# LEOPADMINI.net
KiCad netlist of a schematic drawn in EAGLE
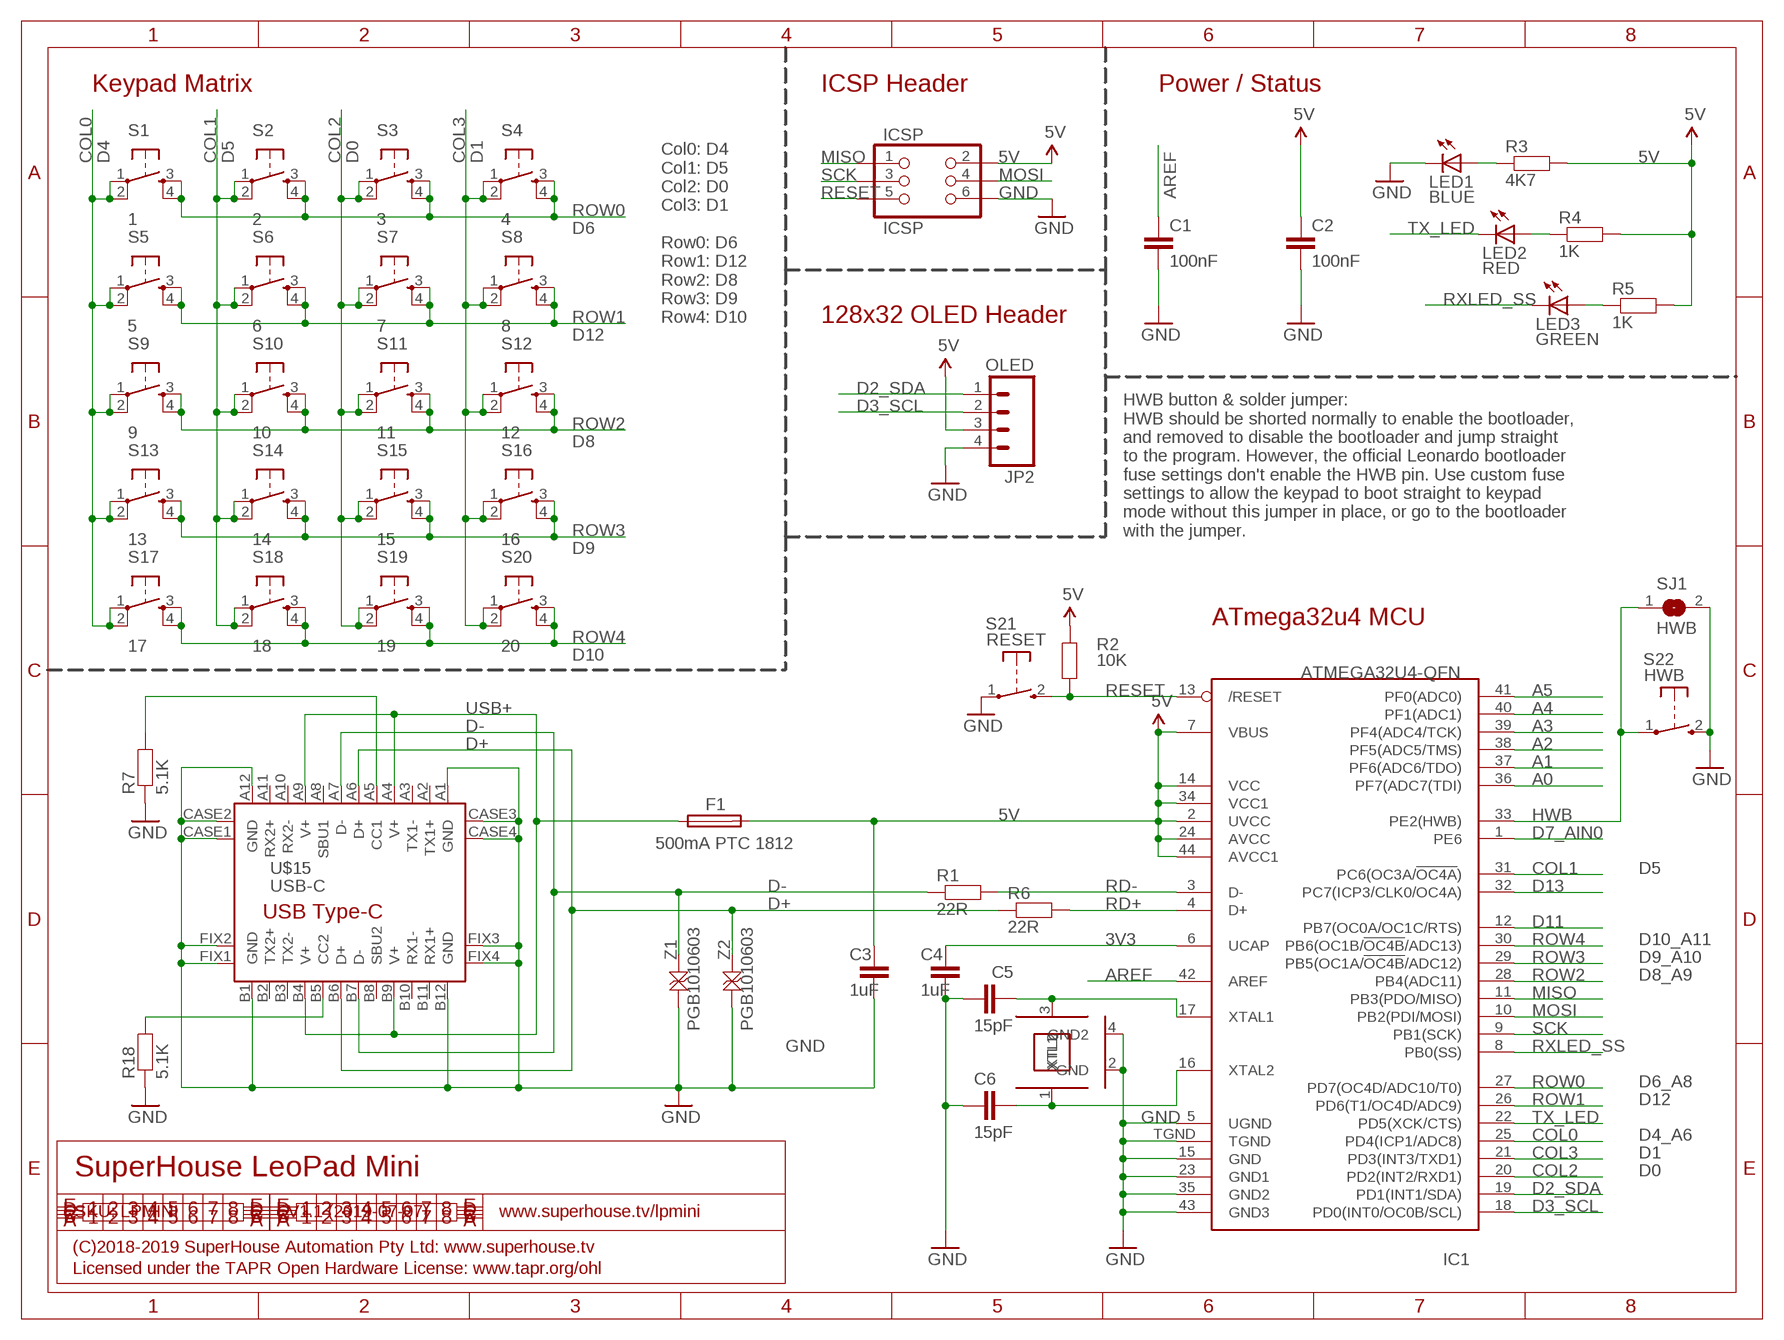
[diagram p0: schematic, sheet 1]

(export (version "E")
  (design (tool "Eeschema 10.0.6"))
  (components
    (comp (ref "C1")
      (value "100nF")
      (footprint "eagle-import:C0603")
      (libsource (lib "eagle-import") (part "CAP0603"))
    )
    (comp (ref "C2")
      (value "100nF")
      (footprint "eagle-import:C0603")
      (libsource (lib "eagle-import") (part "CAP0603"))
    )
    (comp (ref "C3")
      (value "1uF")
      (footprint "eagle-import:C0603")
      (libsource (lib "eagle-import") (part "CAP0603"))
    )
    (comp (ref "C4")
      (value "1uF")
      (footprint "eagle-import:C0603")
      (libsource (lib "eagle-import") (part "CAP0603"))
    )
    (comp (ref "C5")
      (value "15pF")
      (footprint "eagle-import:C0603")
      (libsource (lib "eagle-import") (part "CAP0603"))
    )
    (comp (ref "C6")
      (value "15pF")
      (footprint "eagle-import:C0603")
      (libsource (lib "eagle-import") (part "CAP0603"))
    )
    (comp (ref "F1")
      (value "500mA PTC 1812")
      (footprint "eagle-import:1812")
      (libsource (lib "eagle-import") (part "PTC050"))
    )
    (comp (ref "IC1")
      (value "ATMEGA32U4-QFN")
      (footprint "eagle-import:QFN-44N")
      (libsource (lib "eagle-import") (part "ATMEGA32U4-QFN"))
    )
    (comp (ref "ICSP")
      (value "ICSP")
      (footprint "eagle-import:2X03PTH")
      (libsource (lib "eagle-import") (part "ICSPPTH"))
    )
    (comp (ref "JP2")
      (value "OLED")
      (footprint "eagle-import:1X04")
      (libsource (lib "eagle-import") (part "M04PTH"))
    )
    (comp (ref "LED1")
      (value "BLUE")
      (footprint "eagle-import:LED-0603")
      (libsource (lib "eagle-import") (part "LED0603"))
    )
    (comp (ref "LED2")
      (value "RED")
      (footprint "eagle-import:LED-0603")
      (libsource (lib "eagle-import") (part "LED0603"))
    )
    (comp (ref "LED3")
      (value "GREEN")
      (footprint "eagle-import:LED-0603")
      (libsource (lib "eagle-import") (part "LED0603"))
    )
    (comp (ref "R1")
      (value "22R")
      (footprint "eagle-import:R0603")
      (libsource (lib "eagle-import") (part "RESISTOR0603"))
    )
    (comp (ref "R2")
      (value "10K")
      (footprint "eagle-import:R0603")
      (libsource (lib "eagle-import") (part "RESISTOR0603"))
    )
    (comp (ref "R3")
      (value "4K7")
      (footprint "eagle-import:R0603")
      (libsource (lib "eagle-import") (part "RESISTOR0603"))
    )
    (comp (ref "R4")
      (value "1K")
      (footprint "eagle-import:R0603")
      (libsource (lib "eagle-import") (part "RESISTOR0603"))
    )
    (comp (ref "R5")
      (value "1K")
      (footprint "eagle-import:R0603")
      (libsource (lib "eagle-import") (part "RESISTOR0603"))
    )
    (comp (ref "R6")
      (value "22R")
      (footprint "eagle-import:R0603")
      (libsource (lib "eagle-import") (part "RESISTOR0603"))
    )
    (comp (ref "R7")
      (value "5.1K")
      (footprint "eagle-import:R0603")
      (libsource (lib "eagle-import") (part "RESISTOR0603"))
    )
    (comp (ref "R18")
      (value "5.1K")
      (footprint "eagle-import:R0603")
      (libsource (lib "eagle-import") (part "RESISTOR0603"))
    )
    (comp (ref "S1")
      (value "1")
      (footprint "eagle-import:TACTILE-PTH-6MM")
      (fields (field (name "SPICEPREFIX") "S"))
      (libsource (lib "eagle-import") (part "TAC_SWITCH-PTH-6"))
    )
    (comp (ref "S2")
      (value "2")
      (footprint "eagle-import:TACTILE-PTH-6MM")
      (libsource (lib "eagle-import") (part "TAC_SWITCH-PTH-6"))
    )
    (comp (ref "S3")
      (value "3")
      (footprint "eagle-import:TACTILE-PTH-6MM")
      (libsource (lib "eagle-import") (part "TAC_SWITCH-PTH-6"))
    )
    (comp (ref "S4")
      (value "4")
      (footprint "eagle-import:TACTILE-PTH-6MM")
      (libsource (lib "eagle-import") (part "TAC_SWITCH-PTH-6"))
    )
    (comp (ref "S5")
      (value "5")
      (footprint "eagle-import:TACTILE-PTH-6MM")
      (libsource (lib "eagle-import") (part "TAC_SWITCH-PTH-6"))
    )
    (comp (ref "S6")
      (value "6")
      (footprint "eagle-import:TACTILE-PTH-6MM")
      (libsource (lib "eagle-import") (part "TAC_SWITCH-PTH-6"))
    )
    (comp (ref "S7")
      (value "7")
      (footprint "eagle-import:TACTILE-PTH-6MM")
      (libsource (lib "eagle-import") (part "TAC_SWITCH-PTH-6"))
    )
    (comp (ref "S8")
      (value "8")
      (footprint "eagle-import:TACTILE-PTH-6MM")
      (libsource (lib "eagle-import") (part "TAC_SWITCH-PTH-6"))
    )
    (comp (ref "S9")
      (value "9")
      (footprint "eagle-import:TACTILE-PTH-6MM")
      (libsource (lib "eagle-import") (part "TAC_SWITCH-PTH-6"))
    )
    (comp (ref "S10")
      (value "10")
      (footprint "eagle-import:TACTILE-PTH-6MM")
      (libsource (lib "eagle-import") (part "TAC_SWITCH-PTH-6"))
    )
    (comp (ref "S11")
      (value "11")
      (footprint "eagle-import:TACTILE-PTH-6MM")
      (libsource (lib "eagle-import") (part "TAC_SWITCH-PTH-6"))
    )
    (comp (ref "S12")
      (value "12")
      (footprint "eagle-import:TACTILE-PTH-6MM")
      (libsource (lib "eagle-import") (part "TAC_SWITCH-PTH-6"))
    )
    (comp (ref "S13")
      (value "13")
      (footprint "eagle-import:TACTILE-PTH-6MM")
      (libsource (lib "eagle-import") (part "TAC_SWITCH-PTH-6"))
    )
    (comp (ref "S14")
      (value "14")
      (footprint "eagle-import:TACTILE-PTH-6MM")
      (libsource (lib "eagle-import") (part "TAC_SWITCH-PTH-6"))
    )
    (comp (ref "S15")
      (value "15")
      (footprint "eagle-import:TACTILE-PTH-6MM")
      (libsource (lib "eagle-import") (part "TAC_SWITCH-PTH-6"))
    )
    (comp (ref "S16")
      (value "16")
      (footprint "eagle-import:TACTILE-PTH-6MM")
      (libsource (lib "eagle-import") (part "TAC_SWITCH-PTH-6"))
    )
    (comp (ref "S17")
      (value "17")
      (footprint "eagle-import:TACTILE-PTH-6MM")
      (libsource (lib "eagle-import") (part "TAC_SWITCH-PTH-6"))
    )
    (comp (ref "S18")
      (value "18")
      (footprint "eagle-import:TACTILE-PTH-6MM")
      (libsource (lib "eagle-import") (part "TAC_SWITCH-PTH-6"))
    )
    (comp (ref "S19")
      (value "19")
      (footprint "eagle-import:TACTILE-PTH-6MM")
      (libsource (lib "eagle-import") (part "TAC_SWITCH-PTH-6"))
    )
    (comp (ref "S20")
      (value "20")
      (footprint "eagle-import:TACTILE-PTH-6MM")
      (libsource (lib "eagle-import") (part "TAC_SWITCH-PTH-6"))
    )
    (comp (ref "S21")
      (value "RESET")
      (footprint "eagle-import:TACTILE_SMD_3X4X2")
      (libsource (lib "eagle-import") (part "TAC_SWITCH_2PINSMT"))
    )
    (comp (ref "S22")
      (value "HWB")
      (footprint "eagle-import:TACTILE_SMD_3X4X2")
      (libsource (lib "eagle-import") (part "TAC_SWITCH_2PINSMT"))
    )
    (comp (ref "SJ1")
      (value "HWB")
      (footprint "eagle-import:SJ")
      (libsource (lib "eagle-import") (part "SJN"))
    )
    (comp (ref "U$15")
      (value "USB-C")
      (footprint "eagle-import:USB-C-U52A")
      (libsource (lib "eagle-import") (part "USB-C"))
    )
    (comp (ref "XTL1")
      (value "16MHz")
      (footprint "eagle-import:CRYSTAL-SMD-3X2")
      (libsource (lib "eagle-import") (part "CRYSTAL-GND3X2"))
    )
    (comp (ref "Z1")
      (value "PGB1010603")
      (footprint "eagle-import:TVS0603")
      (libsource (lib "eagle-import") (part "TVS0603"))
    )
    (comp (ref "Z2")
      (value "PGB1010603")
      (footprint "eagle-import:TVS0603")
      (libsource (lib "eagle-import") (part "TVS0603"))
    )
  )
  (nets
    (net (code "1") (name "/3V3") (class "Default")
      (node (ref "C4") (pin "2") (pinfunction "2_2") (pintype "passive"))
      (node (ref "IC1") (pin "6") (pinfunction "UCAP_6") (pintype "bidirectional"))
    )
    (net (code "2") (name "/A0") (class "Default")
      (node (ref "IC1") (pin "36") (pinfunction "PF7(ADC7(TDI)_36") (pintype "bidirectional"))
    )
    (net (code "3") (name "/A1") (class "Default")
      (node (ref "IC1") (pin "37") (pinfunction "PF6(ADC6/TDO)_37") (pintype "bidirectional"))
    )
    (net (code "4") (name "/A2") (class "Default")
      (node (ref "IC1") (pin "38") (pinfunction "PF5(ADC5/TMS)_38") (pintype "bidirectional"))
    )
    (net (code "5") (name "/A3") (class "Default")
      (node (ref "IC1") (pin "39") (pinfunction "PF4(ADC4/TCK)_39") (pintype "bidirectional"))
    )
    (net (code "6") (name "/A4") (class "Default")
      (node (ref "IC1") (pin "40") (pinfunction "PF1(ADC1)_40") (pintype "bidirectional"))
    )
    (net (code "7") (name "/A5") (class "Default")
      (node (ref "IC1") (pin "41") (pinfunction "PF0(ADC0)_41") (pintype "bidirectional"))
    )
    (net (code "8") (name "/AREF") (class "Default")
      (node (ref "C1") (pin "1") (pinfunction "1_1") (pintype "passive"))
      (node (ref "IC1") (pin "42") (pinfunction "AREF_42") (pintype "bidirectional"))
    )
    (net (code "9") (name "/COL0") (class "Default")
      (node (ref "IC1") (pin "25") (pinfunction "PD4(ICP1/ADC8)_25") (pintype "bidirectional"))
      (node (ref "S1") (pin "1") (pinfunction "1_1") (pintype "passive"))
      (node (ref "S1") (pin "2") (pinfunction "2_2") (pintype "passive"))
      (node (ref "S13") (pin "1") (pinfunction "1_1") (pintype "passive"))
      (node (ref "S13") (pin "2") (pinfunction "2_2") (pintype "passive"))
      (node (ref "S17") (pin "1") (pinfunction "1_1") (pintype "passive"))
      (node (ref "S17") (pin "2") (pinfunction "2_2") (pintype "passive"))
      (node (ref "S5") (pin "1") (pinfunction "1_1") (pintype "passive"))
      (node (ref "S5") (pin "2") (pinfunction "2_2") (pintype "passive"))
      (node (ref "S9") (pin "1") (pinfunction "1_1") (pintype "passive"))
      (node (ref "S9") (pin "2") (pinfunction "2_2") (pintype "passive"))
    )
    (net (code "10") (name "/COL1") (class "Default")
      (node (ref "IC1") (pin "31") (pinfunction "PC6(OC3A/~{OC4A})_31") (pintype "bidirectional"))
      (node (ref "S10") (pin "1") (pinfunction "1_1") (pintype "passive"))
      (node (ref "S10") (pin "2") (pinfunction "2_2") (pintype "passive"))
      (node (ref "S14") (pin "1") (pinfunction "1_1") (pintype "passive"))
      (node (ref "S14") (pin "2") (pinfunction "2_2") (pintype "passive"))
      (node (ref "S18") (pin "1") (pinfunction "1_1") (pintype "passive"))
      (node (ref "S18") (pin "2") (pinfunction "2_2") (pintype "passive"))
      (node (ref "S2") (pin "1") (pinfunction "1_1") (pintype "passive"))
      (node (ref "S2") (pin "2") (pinfunction "2_2") (pintype "passive"))
      (node (ref "S6") (pin "1") (pinfunction "1_1") (pintype "passive"))
      (node (ref "S6") (pin "2") (pinfunction "2_2") (pintype "passive"))
    )
    (net (code "11") (name "/COL2") (class "Default")
      (node (ref "IC1") (pin "20") (pinfunction "PD2(INT2/RXD1)_20") (pintype "bidirectional"))
      (node (ref "S11") (pin "1") (pinfunction "1_1") (pintype "passive"))
      (node (ref "S11") (pin "2") (pinfunction "2_2") (pintype "passive"))
      (node (ref "S15") (pin "1") (pinfunction "1_1") (pintype "passive"))
      (node (ref "S15") (pin "2") (pinfunction "2_2") (pintype "passive"))
      (node (ref "S19") (pin "1") (pinfunction "1_1") (pintype "passive"))
      (node (ref "S19") (pin "2") (pinfunction "2_2") (pintype "passive"))
      (node (ref "S3") (pin "1") (pinfunction "1_1") (pintype "passive"))
      (node (ref "S3") (pin "2") (pinfunction "2_2") (pintype "passive"))
      (node (ref "S7") (pin "1") (pinfunction "1_1") (pintype "passive"))
      (node (ref "S7") (pin "2") (pinfunction "2_2") (pintype "passive"))
    )
    (net (code "12") (name "/COL3") (class "Default")
      (node (ref "IC1") (pin "21") (pinfunction "PD3(INT3/TXD1)_21") (pintype "bidirectional"))
      (node (ref "S12") (pin "1") (pinfunction "1_1") (pintype "passive"))
      (node (ref "S12") (pin "2") (pinfunction "2_2") (pintype "passive"))
      (node (ref "S16") (pin "1") (pinfunction "1_1") (pintype "passive"))
      (node (ref "S16") (pin "2") (pinfunction "2_2") (pintype "passive"))
      (node (ref "S20") (pin "1") (pinfunction "1_1") (pintype "passive"))
      (node (ref "S20") (pin "2") (pinfunction "2_2") (pintype "passive"))
      (node (ref "S4") (pin "1") (pinfunction "1_1") (pintype "passive"))
      (node (ref "S4") (pin "2") (pinfunction "2_2") (pintype "passive"))
      (node (ref "S8") (pin "1") (pinfunction "1_1") (pintype "passive"))
      (node (ref "S8") (pin "2") (pinfunction "2_2") (pintype "passive"))
    )
    (net (code "13") (name "/D+") (class "Default")
      (node (ref "R6") (pin "1") (pinfunction "1_1") (pintype "passive"))
      (node (ref "U$15") (pin "A6") (pinfunction "D+_A6") (pintype "bidirectional"))
      (node (ref "U$15") (pin "B6") (pinfunction "D+_B6") (pintype "bidirectional"))
      (node (ref "Z2") (pin "2") (pinfunction "2_2") (pintype "passive"))
    )
    (net (code "14") (name "/D-") (class "Default")
      (node (ref "R1") (pin "1") (pinfunction "1_1") (pintype "passive"))
      (node (ref "U$15") (pin "A7") (pinfunction "D-_A7") (pintype "bidirectional"))
      (node (ref "U$15") (pin "B7") (pinfunction "D-_B7") (pintype "bidirectional"))
      (node (ref "Z1") (pin "2") (pinfunction "2_2") (pintype "passive"))
    )
    (net (code "15") (name "/D2_SDA") (class "Default")
      (node (ref "IC1") (pin "19") (pinfunction "PD1(INT1/SDA)_19") (pintype "bidirectional"))
      (node (ref "JP2") (pin "1") (pinfunction "1_1") (pintype "passive"))
    )
    (net (code "16") (name "/D3_SCL") (class "Default")
      (node (ref "IC1") (pin "18") (pinfunction "PD0(INT0/OC0B/SCL)_18") (pintype "bidirectional"))
      (node (ref "JP2") (pin "2") (pinfunction "2_2") (pintype "passive"))
    )
    (net (code "17") (name "/D7_AIN0") (class "Default")
      (node (ref "IC1") (pin "1") (pinfunction "PE6_1") (pintype "bidirectional"))
    )
    (net (code "18") (name "/D11") (class "Default")
      (node (ref "IC1") (pin "12") (pinfunction "PB7(OC0A/OC1C/RTS)_12") (pintype "bidirectional"))
    )
    (net (code "19") (name "/D13") (class "Default")
      (node (ref "IC1") (pin "32") (pinfunction "PC7(ICP3/CLK0/OC4A)_32") (pintype "bidirectional"))
    )
    (net (code "20") (name "/HWB") (class "Default")
      (node (ref "IC1") (pin "33") (pinfunction "PE2(HWB)_33") (pintype "bidirectional"))
      (node (ref "S22") (pin "1") (pinfunction "P_1") (pintype "passive"))
      (node (ref "SJ1") (pin "1") (pinfunction "1_1") (pintype "passive"))
    )
    (net (code "21") (name "/MISO") (class "Default")
      (node (ref "IC1") (pin "11") (pinfunction "PB3(PDO/MISO)_11") (pintype "bidirectional"))
      (node (ref "ICSP") (pin "1") (pinfunction "1_1") (pintype "passive"))
    )
    (net (code "22") (name "/MOSI") (class "Default")
      (node (ref "IC1") (pin "10") (pinfunction "PB2(PDI/MOSI)_10") (pintype "bidirectional"))
      (node (ref "ICSP") (pin "4") (pinfunction "4_4") (pintype "passive"))
    )
    (net (code "23") (name "/RD+") (class "Default")
      (node (ref "IC1") (pin "4") (pinfunction "D+_4") (pintype "bidirectional"))
      (node (ref "R6") (pin "2") (pinfunction "2_2") (pintype "passive"))
    )
    (net (code "24") (name "/RD-") (class "Default")
      (node (ref "IC1") (pin "3") (pinfunction "D-_3") (pintype "bidirectional"))
      (node (ref "R1") (pin "2") (pinfunction "2_2") (pintype "passive"))
    )
    (net (code "25") (name "/RESET") (class "Default")
      (node (ref "IC1") (pin "13") (pinfunction "/RESET_13") (pintype "bidirectional"))
      (node (ref "ICSP") (pin "5") (pinfunction "5_5") (pintype "passive"))
      (node (ref "R2") (pin "1") (pinfunction "1_1") (pintype "passive"))
      (node (ref "S21") (pin "2") (pinfunction "S_2") (pintype "passive"))
    )
    (net (code "26") (name "/ROW0") (class "Default")
      (node (ref "IC1") (pin "27") (pinfunction "PD7(OC4D/ADC10/T0)_27") (pintype "bidirectional"))
      (node (ref "S1") (pin "3") (pinfunction "3_3") (pintype "passive"))
      (node (ref "S1") (pin "4") (pinfunction "4_4") (pintype "passive"))
      (node (ref "S2") (pin "3") (pinfunction "3_3") (pintype "passive"))
      (node (ref "S2") (pin "4") (pinfunction "4_4") (pintype "passive"))
      (node (ref "S3") (pin "3") (pinfunction "3_3") (pintype "passive"))
      (node (ref "S3") (pin "4") (pinfunction "4_4") (pintype "passive"))
      (node (ref "S4") (pin "3") (pinfunction "3_3") (pintype "passive"))
      (node (ref "S4") (pin "4") (pinfunction "4_4") (pintype "passive"))
    )
    (net (code "27") (name "/ROW1") (class "Default")
      (node (ref "IC1") (pin "26") (pinfunction "PD6(T1/OC4D/ADC9)_26") (pintype "bidirectional"))
      (node (ref "S5") (pin "3") (pinfunction "3_3") (pintype "passive"))
      (node (ref "S5") (pin "4") (pinfunction "4_4") (pintype "passive"))
      (node (ref "S6") (pin "3") (pinfunction "3_3") (pintype "passive"))
      (node (ref "S6") (pin "4") (pinfunction "4_4") (pintype "passive"))
      (node (ref "S7") (pin "3") (pinfunction "3_3") (pintype "passive"))
      (node (ref "S7") (pin "4") (pinfunction "4_4") (pintype "passive"))
      (node (ref "S8") (pin "3") (pinfunction "3_3") (pintype "passive"))
      (node (ref "S8") (pin "4") (pinfunction "4_4") (pintype "passive"))
    )
    (net (code "28") (name "/ROW2") (class "Default")
      (node (ref "IC1") (pin "28") (pinfunction "PB4(ADC11)_28") (pintype "bidirectional"))
      (node (ref "S10") (pin "3") (pinfunction "3_3") (pintype "passive"))
      (node (ref "S10") (pin "4") (pinfunction "4_4") (pintype "passive"))
      (node (ref "S11") (pin "3") (pinfunction "3_3") (pintype "passive"))
      (node (ref "S11") (pin "4") (pinfunction "4_4") (pintype "passive"))
      (node (ref "S12") (pin "3") (pinfunction "3_3") (pintype "passive"))
      (node (ref "S12") (pin "4") (pinfunction "4_4") (pintype "passive"))
      (node (ref "S9") (pin "3") (pinfunction "3_3") (pintype "passive"))
      (node (ref "S9") (pin "4") (pinfunction "4_4") (pintype "passive"))
    )
    (net (code "29") (name "/ROW3") (class "Default")
      (node (ref "IC1") (pin "29") (pinfunction "PB5(OC1A/~{OC4B}/ADC12)_29") (pintype "bidirectional"))
      (node (ref "S13") (pin "3") (pinfunction "3_3") (pintype "passive"))
      (node (ref "S13") (pin "4") (pinfunction "4_4") (pintype "passive"))
      (node (ref "S14") (pin "3") (pinfunction "3_3") (pintype "passive"))
      (node (ref "S14") (pin "4") (pinfunction "4_4") (pintype "passive"))
      (node (ref "S15") (pin "3") (pinfunction "3_3") (pintype "passive"))
      (node (ref "S15") (pin "4") (pinfunction "4_4") (pintype "passive"))
      (node (ref "S16") (pin "3") (pinfunction "3_3") (pintype "passive"))
      (node (ref "S16") (pin "4") (pinfunction "4_4") (pintype "passive"))
    )
    (net (code "30") (name "/ROW4") (class "Default")
      (node (ref "IC1") (pin "30") (pinfunction "PB6(OC1B/~{OC4B}/ADC13)_30") (pintype "bidirectional"))
      (node (ref "S17") (pin "3") (pinfunction "3_3") (pintype "passive"))
      (node (ref "S17") (pin "4") (pinfunction "4_4") (pintype "passive"))
      (node (ref "S18") (pin "3") (pinfunction "3_3") (pintype "passive"))
      (node (ref "S18") (pin "4") (pinfunction "4_4") (pintype "passive"))
      (node (ref "S19") (pin "3") (pinfunction "3_3") (pintype "passive"))
      (node (ref "S19") (pin "4") (pinfunction "4_4") (pintype "passive"))
      (node (ref "S20") (pin "3") (pinfunction "3_3") (pintype "passive"))
      (node (ref "S20") (pin "4") (pinfunction "4_4") (pintype "passive"))
    )
    (net (code "31") (name "/RXLED_SS") (class "Default")
      (node (ref "IC1") (pin "8") (pinfunction "PB0(SS)_8") (pintype "bidirectional"))
      (node (ref "LED3") (pin "C") (pinfunction "C_C") (pintype "passive"))
    )
    (net (code "32") (name "/SCK") (class "Default")
      (node (ref "IC1") (pin "9") (pinfunction "PB1(SCK)_9") (pintype "bidirectional"))
      (node (ref "ICSP") (pin "3") (pinfunction "3_3") (pintype "passive"))
    )
    (net (code "33") (name "/TX_LED") (class "Default")
      (node (ref "IC1") (pin "22") (pinfunction "PD5(XCK/CTS)_22") (pintype "bidirectional"))
      (node (ref "LED2") (pin "C") (pinfunction "C_C") (pintype "passive"))
    )
    (net (code "34") (name "/USB+") (class "Default")
      (node (ref "F1") (pin "1") (pinfunction "1_1") (pintype "passive"))
      (node (ref "U$15") (pin "A4") (pinfunction "V+_A4") (pintype "power_in"))
      (node (ref "U$15") (pin "A9") (pinfunction "V+_A9") (pintype "power_in"))
      (node (ref "U$15") (pin "B4") (pinfunction "V+_B4") (pintype "power_in"))
      (node (ref "U$15") (pin "B9") (pinfunction "V+_B9") (pintype "power_in"))
    )
    (net (code "35") (name "5V") (class "Default")
      (node (ref "C2") (pin "1") (pinfunction "1_1") (pintype "passive"))
      (node (ref "C3") (pin "1") (pinfunction "1_1") (pintype "passive"))
      (node (ref "F1") (pin "2") (pinfunction "2_2") (pintype "passive"))
      (node (ref "IC1") (pin "14") (pinfunction "VCC_14") (pintype "bidirectional"))
      (node (ref "IC1") (pin "2") (pinfunction "UVCC_2") (pintype "bidirectional"))
      (node (ref "IC1") (pin "24") (pinfunction "AVCC_24") (pintype "bidirectional"))
      (node (ref "IC1") (pin "34") (pinfunction "VCC1_34") (pintype "bidirectional"))
      (node (ref "IC1") (pin "44") (pinfunction "AVCC1_44") (pintype "bidirectional"))
      (node (ref "IC1") (pin "7") (pinfunction "VBUS_7") (pintype "bidirectional"))
      (node (ref "ICSP") (pin "2") (pinfunction "2_2") (pintype "passive"))
      (node (ref "JP2") (pin "3") (pinfunction "3_3") (pintype "passive"))
      (node (ref "R2") (pin "2") (pinfunction "2_2") (pintype "passive"))
      (node (ref "R3") (pin "2") (pinfunction "2_2") (pintype "passive"))
      (node (ref "R4") (pin "2") (pinfunction "2_2") (pintype "passive"))
      (node (ref "R5") (pin "2") (pinfunction "2_2") (pintype "passive"))
    )
    (net (code "36") (name "GND") (class "Default")
      (node (ref "C1") (pin "2") (pinfunction "2_2") (pintype "passive"))
      (node (ref "C2") (pin "2") (pinfunction "2_2") (pintype "passive"))
      (node (ref "C3") (pin "2") (pinfunction "2_2") (pintype "passive"))
      (node (ref "C4") (pin "1") (pinfunction "1_1") (pintype "passive"))
      (node (ref "C5") (pin "1") (pinfunction "1_1") (pintype "passive"))
      (node (ref "C6") (pin "1") (pinfunction "1_1") (pintype "passive"))
      (node (ref "IC1") (pin "15") (pinfunction "GND_15") (pintype "bidirectional"))
      (node (ref "IC1") (pin "23") (pinfunction "GND1_23") (pintype "bidirectional"))
      (node (ref "IC1") (pin "35") (pinfunction "GND2_35") (pintype "bidirectional"))
      (node (ref "IC1") (pin "43") (pinfunction "GND3_43") (pintype "bidirectional"))
      (node (ref "IC1") (pin "5") (pinfunction "UGND_5") (pintype "bidirectional"))
      (node (ref "IC1") (pin "TGND") (pinfunction "TGND_TGND") (pintype "bidirectional"))
      (node (ref "ICSP") (pin "6") (pinfunction "6_6") (pintype "passive"))
      (node (ref "JP2") (pin "4") (pinfunction "4_4") (pintype "passive"))
      (node (ref "LED1") (pin "C") (pinfunction "C_C") (pintype "passive"))
      (node (ref "R18") (pin "1") (pinfunction "1_1") (pintype "passive"))
      (node (ref "R7") (pin "1") (pinfunction "1_1") (pintype "passive"))
      (node (ref "S21") (pin "1") (pinfunction "P_1") (pintype "passive"))
      (node (ref "S22") (pin "2") (pinfunction "S_2") (pintype "passive"))
      (node (ref "SJ1") (pin "2") (pinfunction "2_2") (pintype "passive"))
      (node (ref "U$15") (pin "A1") (pinfunction "GND_A1") (pintype "power_in"))
      (node (ref "U$15") (pin "A12") (pinfunction "GND_A12") (pintype "power_in"))
      (node (ref "U$15") (pin "B1") (pinfunction "GND_B1") (pintype "power_in"))
      (node (ref "U$15") (pin "B12") (pinfunction "GND_B12") (pintype "power_in"))
      (node (ref "U$15") (pin "CASE1") (pinfunction "GND_CASE1") (pintype "power_in"))
      (node (ref "U$15") (pin "CASE2") (pinfunction "GND_CASE2") (pintype "power_in"))
      (node (ref "U$15") (pin "CASE3") (pinfunction "GND_CASE3") (pintype "power_in"))
      (node (ref "U$15") (pin "CASE4") (pinfunction "GND_CASE4") (pintype "power_in"))
      (node (ref "U$15") (pin "FIX1") (pinfunction "GND_FIX1") (pintype "power_in"))
      (node (ref "U$15") (pin "FIX2") (pinfunction "GND_FIX2") (pintype "power_in"))
      (node (ref "U$15") (pin "FIX3") (pinfunction "GND_FIX3") (pintype "power_in"))
      (node (ref "U$15") (pin "FIX4") (pinfunction "GND_FIX4") (pintype "power_in"))
      (node (ref "XTL1") (pin "2") (pinfunction "GND_2") (pintype "bidirectional"))
      (node (ref "XTL1") (pin "4") (pinfunction "GND2_4") (pintype "bidirectional"))
      (node (ref "Z1") (pin "1") (pinfunction "1_1") (pintype "passive"))
      (node (ref "Z2") (pin "1") (pinfunction "1_1") (pintype "passive"))
    )
    (net (code "37") (name "Net-(IC1-XTAL1)") (class "Default")
      (node (ref "C5") (pin "2") (pinfunction "2_2") (pintype "passive"))
      (node (ref "IC1") (pin "17") (pinfunction "XTAL1_17") (pintype "bidirectional"))
      (node (ref "XTL1") (pin "3") (pinfunction "XTL2_3") (pintype "bidirectional"))
    )
    (net (code "38") (name "Net-(IC1-XTAL2)") (class "Default")
      (node (ref "C6") (pin "2") (pinfunction "2_2") (pintype "passive"))
      (node (ref "IC1") (pin "16") (pinfunction "XTAL2_16") (pintype "bidirectional"))
      (node (ref "XTL1") (pin "1") (pinfunction "XTL1_1") (pintype "bidirectional"))
    )
    (net (code "39") (name "Net-(LED1-PadA)") (class "Default")
      (node (ref "LED1") (pin "A") (pinfunction "A_A") (pintype "passive"))
      (node (ref "R3") (pin "1") (pinfunction "1_1") (pintype "passive"))
    )
    (net (code "40") (name "Net-(LED2-PadA)") (class "Default")
      (node (ref "LED2") (pin "A") (pinfunction "A_A") (pintype "passive"))
      (node (ref "R4") (pin "1") (pinfunction "1_1") (pintype "passive"))
    )
    (net (code "41") (name "Net-(LED3-PadA)") (class "Default")
      (node (ref "LED3") (pin "A") (pinfunction "A_A") (pintype "passive"))
      (node (ref "R5") (pin "1") (pinfunction "1_1") (pintype "passive"))
    )
    (net (code "42") (name "Net-(U$15-CC1)") (class "Default")
      (node (ref "R7") (pin "2") (pinfunction "2_2") (pintype "passive"))
      (node (ref "U$15") (pin "A5") (pinfunction "CC1_A5") (pintype "bidirectional"))
    )
    (net (code "43") (name "Net-(U$15-CC2)") (class "Default")
      (node (ref "R18") (pin "2") (pinfunction "2_2") (pintype "passive"))
      (node (ref "U$15") (pin "B5") (pinfunction "CC2_B5") (pintype "bidirectional"))
    )
    (net (code "44") (name "unconnected-(U$15-RX1+-PadB11)") (class "Default")
      (node (ref "U$15") (pin "B11") (pinfunction "RX1+_B11") (pintype "bidirectional"))
    )
    (net (code "45") (name "unconnected-(U$15-RX1--PadB10)") (class "Default")
      (node (ref "U$15") (pin "B10") (pinfunction "RX1-_B10") (pintype "bidirectional"))
    )
    (net (code "46") (name "unconnected-(U$15-RX2+-PadA11)") (class "Default")
      (node (ref "U$15") (pin "A11") (pinfunction "RX2+_A11") (pintype "bidirectional"))
    )
    (net (code "47") (name "unconnected-(U$15-RX2--PadA10)") (class "Default")
      (node (ref "U$15") (pin "A10") (pinfunction "RX2-_A10") (pintype "bidirectional"))
    )
    (net (code "48") (name "unconnected-(U$15-SBU1-PadA8)") (class "Default")
      (node (ref "U$15") (pin "A8") (pinfunction "SBU1_A8") (pintype "bidirectional"))
    )
    (net (code "49") (name "unconnected-(U$15-SBU2-PadB8)") (class "Default")
      (node (ref "U$15") (pin "B8") (pinfunction "SBU2_B8") (pintype "bidirectional"))
    )
    (net (code "50") (name "unconnected-(U$15-TX1+-PadA2)") (class "Default")
      (node (ref "U$15") (pin "A2") (pinfunction "TX1+_A2") (pintype "bidirectional"))
    )
    (net (code "51") (name "unconnected-(U$15-TX1--PadA3)") (class "Default")
      (node (ref "U$15") (pin "A3") (pinfunction "TX1-_A3") (pintype "bidirectional"))
    )
    (net (code "52") (name "unconnected-(U$15-TX2+-PadB2)") (class "Default")
      (node (ref "U$15") (pin "B2") (pinfunction "TX2+_B2") (pintype "bidirectional"))
    )
    (net (code "53") (name "unconnected-(U$15-TX2--PadB3)") (class "Default")
      (node (ref "U$15") (pin "B3") (pinfunction "TX2-_B3") (pintype "bidirectional"))
    )
  )
)
